# 6coils-1-discrete.net
KiCad netlist of a schematic drawn in EasyEDA
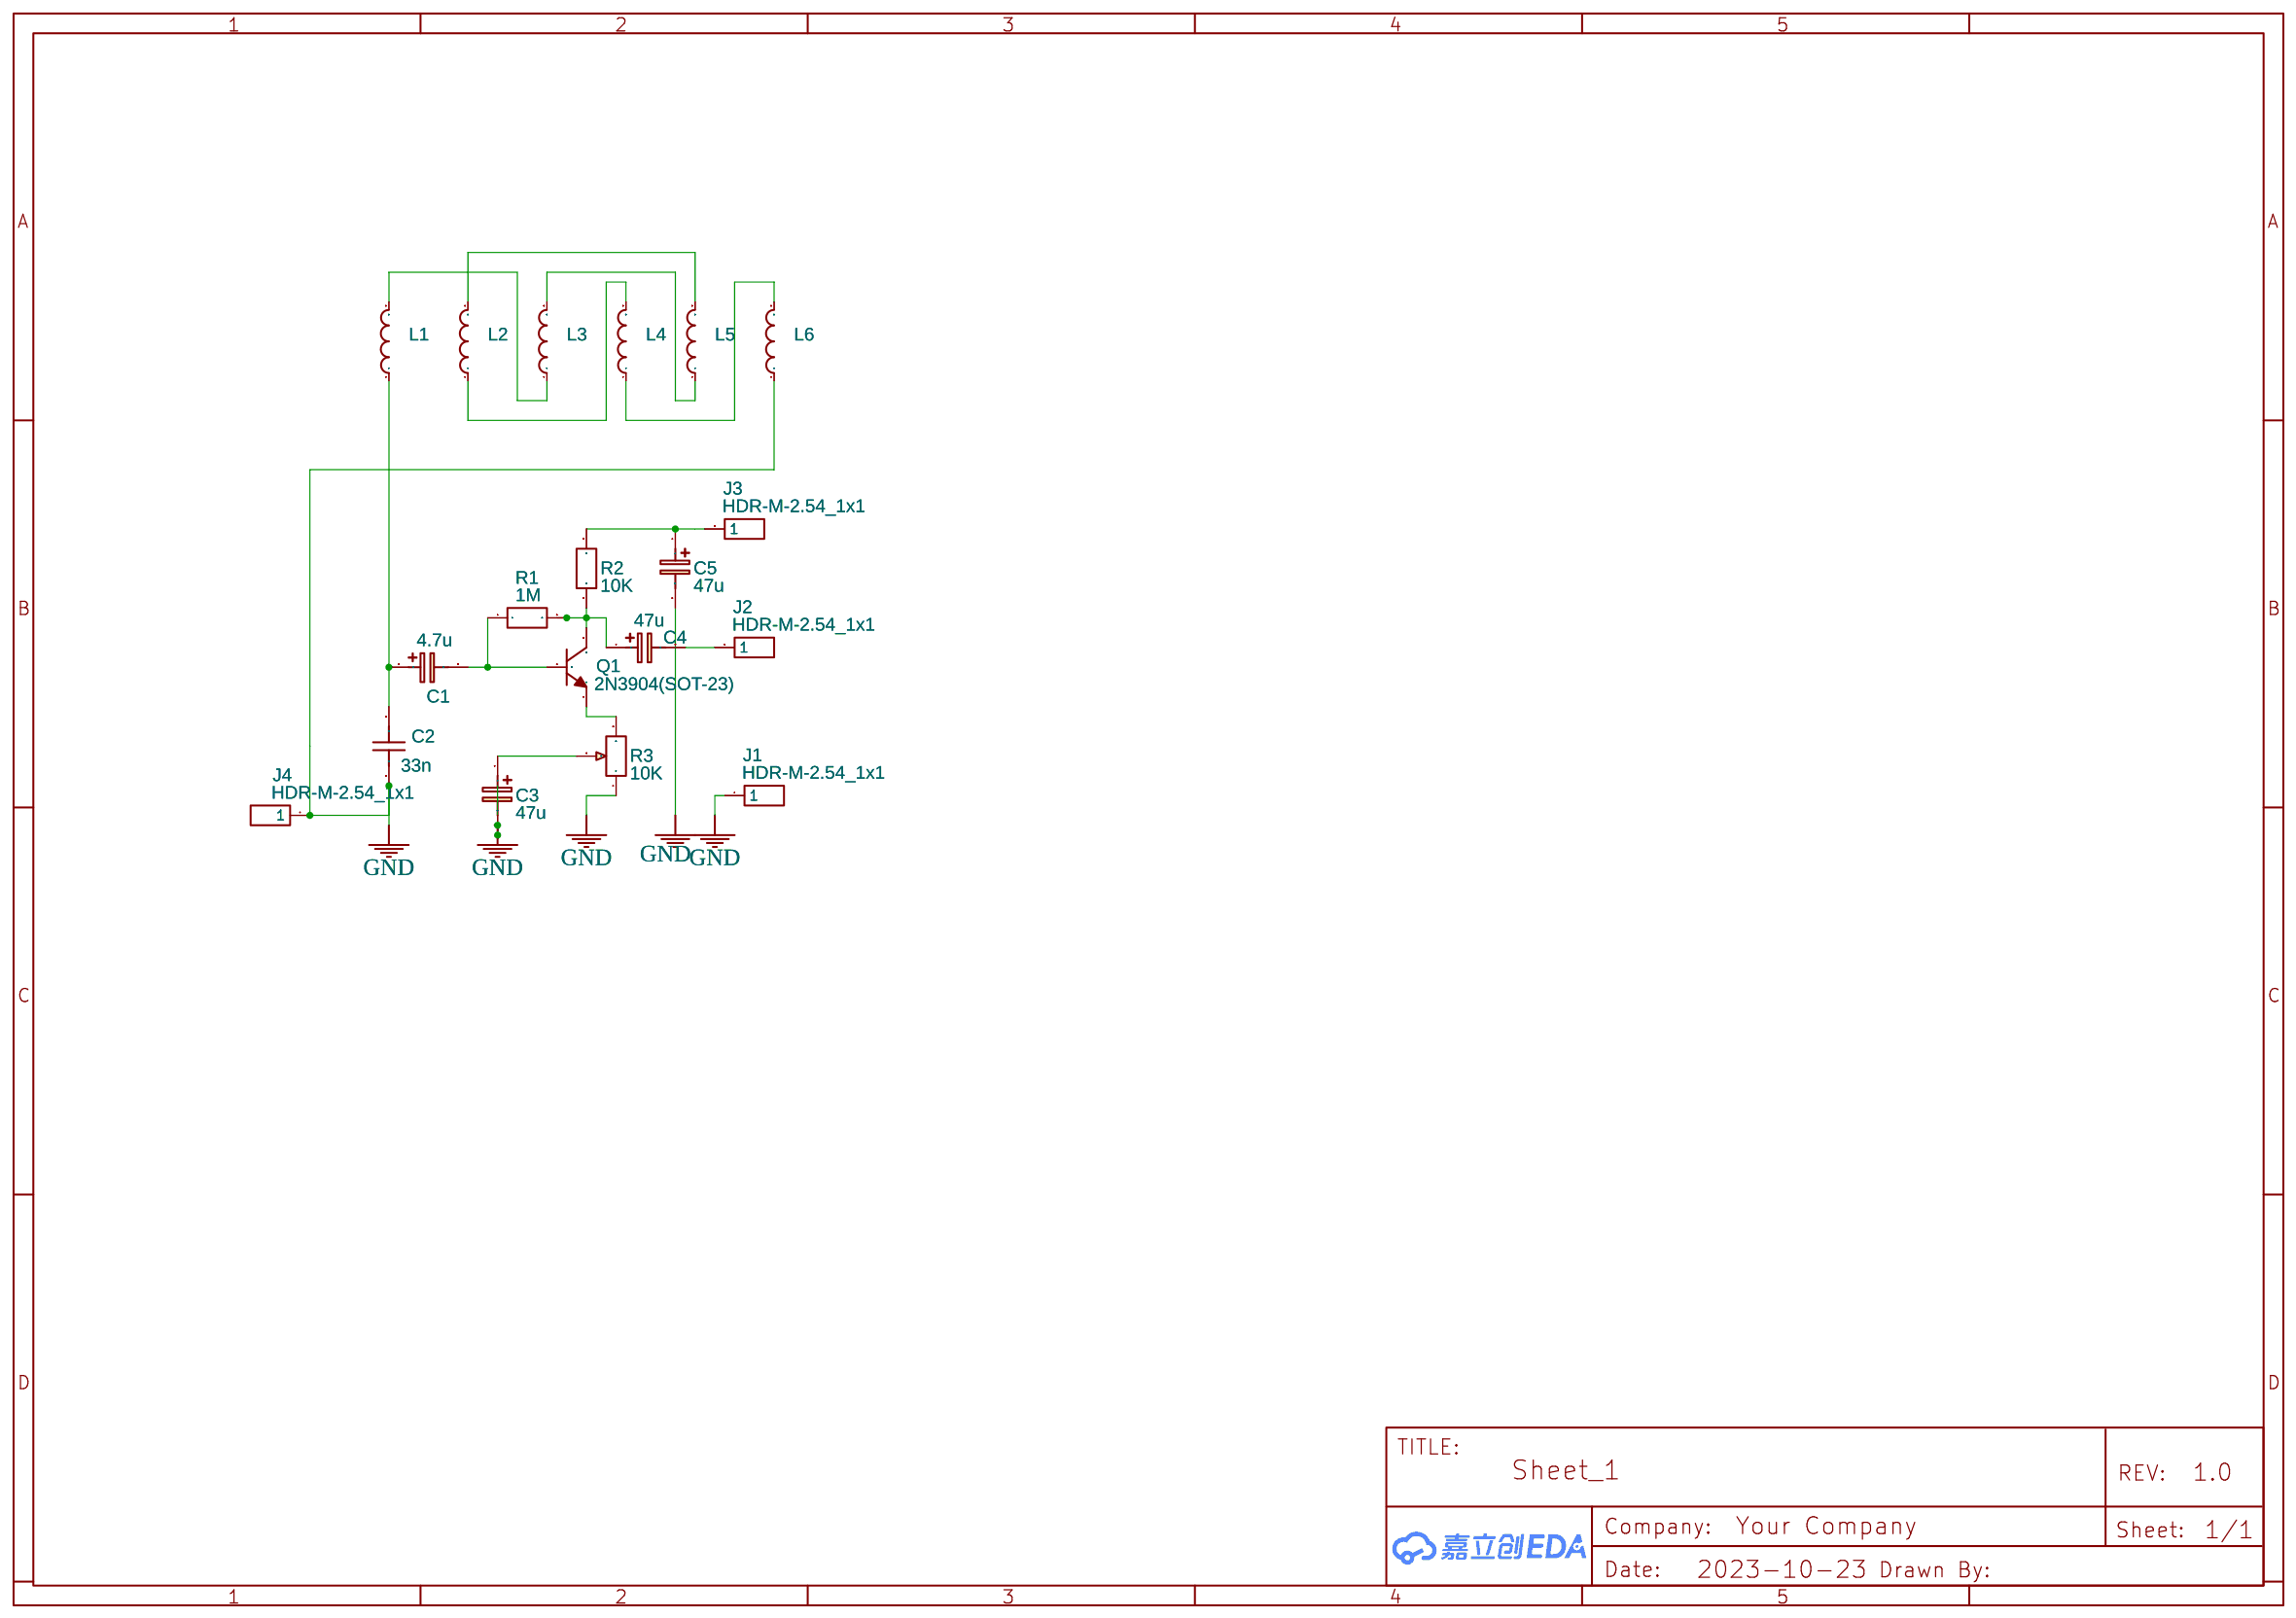
[diagram p0: schematic sheet]

(export (version "E")
  (design (tool "Eeschema 10.0.6"))
  (components
    (comp (ref "C1") (value "4.7u") (libsource (lib "") (part "C_Tan_SMD_A_EU_1")))
    (comp (ref "C2") (value "33n") (libsource (lib "") (part "C_0603_US")))
    (comp (ref "C3") (value "47u") (libsource (lib "") (part "C_Tan_SMD_A_EU")))
    (comp (ref "C4") (value "47u") (libsource (lib "") (part "C_Tan_SMD_A_EU_3")))
    (comp (ref "C5") (value "47u") (libsource (lib "") (part "C_Tan_SMD_A_EU_2")))
    (comp (ref "J1")
      (value "HDR-M-2.54_1x1")
      (fields (field (name "BOM_Supplier Part") "C81276"))
      (libsource (lib "") (part "HDR-M-2.54_1x1"))
    )
    (comp (ref "J2")
      (value "HDR-M-2.54_1x1")
      (fields (field (name "BOM_Supplier Part") "C81276"))
      (libsource (lib "") (part "HDR-M-2.54_1x1"))
    )
    (comp (ref "J3")
      (value "HDR-M-2.54_1x1")
      (fields (field (name "BOM_Supplier Part") "C81276"))
      (libsource (lib "") (part "HDR-M-2.54_1x1"))
    )
    (comp (ref "J4")
      (value "HDR-M-2.54_1x1")
      (fields (field (name "BOM_Supplier Part") "C81276"))
      (libsource (lib "") (part "HDR-M-2.54_1x1_1"))
    )
    (comp (ref "L1")
      (value "INDUCTOR_SMD:L_COILCRAFT_XXL4040")
      (fields (field (name "Manufacturer Part") "Inductor_SMD:L_Coilcraft_XxL4040"))
      (libsource (lib "") (part "INDUCTOR_SMD{colon}L_COILCRAFT_XXL4040_1"))
    )
    (comp (ref "L2")
      (value "INDUCTOR_SMD:L_COILCRAFT_XXL4040")
      (fields (field (name "Manufacturer Part") "Inductor_SMD:L_Coilcraft_XxL4040"))
      (libsource (lib "") (part "INDUCTOR_SMD{colon}L_COILCRAFT_XXL4040_1"))
    )
    (comp (ref "L3")
      (value "INDUCTOR_SMD:L_COILCRAFT_XXL4040")
      (fields (field (name "Manufacturer Part") "Inductor_SMD:L_Coilcraft_XxL4040"))
      (libsource (lib "") (part "INDUCTOR_SMD{colon}L_COILCRAFT_XXL4040"))
    )
    (comp (ref "L4")
      (value "INDUCTOR_SMD:L_COILCRAFT_XXL4040")
      (fields (field (name "Manufacturer Part") "Inductor_SMD:L_Coilcraft_XxL4040"))
      (libsource (lib "") (part "INDUCTOR_SMD{colon}L_COILCRAFT_XXL4040"))
    )
    (comp (ref "L5")
      (value "INDUCTOR_SMD:L_COILCRAFT_XXL4040")
      (fields (field (name "Manufacturer Part") "Inductor_SMD:L_Coilcraft_XxL4040"))
      (libsource (lib "") (part "INDUCTOR_SMD{colon}L_COILCRAFT_XXL4040"))
    )
    (comp (ref "L6")
      (value "INDUCTOR_SMD:L_COILCRAFT_XXL4040")
      (fields (field (name "Manufacturer Part") "Inductor_SMD:L_Coilcraft_XxL4040"))
      (libsource (lib "") (part "INDUCTOR_SMD{colon}L_COILCRAFT_XXL4040"))
    )
    (comp (ref "Q1")
      (value "2N3904(SOT-23)")
      (fields
        (field (name "BOM_Manufacturer Part") "2n3904S-RTK/PS")
        (field (name "BOM_Supplier Part") "C18536")
      )
      (libsource (lib "") (part "2N3904(SOT-23)"))
    )
    (comp (ref "R1") (value "1M") (libsource (lib "") (part "R_0603_EU_1")))
    (comp (ref "R2") (value "10K") (libsource (lib "") (part "R_0603_EU")))
    (comp (ref "R3")
      (value "10K")
      (fields (field (name "Manufacturer Part") "RM063-103 10K") (field (name "Manufacturer") "JML"))
      (libsource (lib "") (part "RM063-103 10K"))
    )
  )
  (nets
    (net (code "1") (name "GND") (class "Default")
      (node (ref "C2") (pin "1") (pinfunction "1_1") (pintype "unspecified"))
      (node (ref "C3") (pin "2") (pinfunction "2_2") (pintype "unspecified"))
      (node (ref "C5") (pin "2") (pinfunction "2_2") (pintype "unspecified"))
      (node (ref "J1") (pin "1") (pinfunction "1_1") (pintype "input"))
      (node (ref "J4") (pin "1") (pinfunction "1_1") (pintype "input"))
      (node (ref "L6") (pin "1") (pinfunction "1_1") (pintype "unspecified"))
      (node (ref "R3") (pin "1") (pinfunction "1_1") (pintype "input"))
    )
    (net (code "2") (name "Net-(C1-Pad1)") (class "Default")
      (node (ref "C1") (pin "1") (pinfunction "1_1") (pintype "unspecified"))
      (node (ref "C2") (pin "2") (pinfunction "2_2") (pintype "unspecified"))
      (node (ref "L1") (pin "1") (pinfunction "1_1") (pintype "unspecified"))
    )
    (net (code "3") (name "Net-(C3-Pad1)") (class "Default")
      (node (ref "C3") (pin "1") (pinfunction "1_1") (pintype "unspecified"))
      (node (ref "R3") (pin "2") (pinfunction "2_2") (pintype "input"))
    )
    (net (code "4") (name "Net-(C4-Pad2)") (class "Default")
      (node (ref "C4") (pin "2") (pinfunction "2_2") (pintype "unspecified"))
      (node (ref "J2") (pin "1") (pinfunction "1_1") (pintype "input"))
    )
    (net (code "5") (name "Net-(C5-Pad1)") (class "Default")
      (node (ref "C5") (pin "1") (pinfunction "1_1") (pintype "unspecified"))
      (node (ref "J3") (pin "1") (pinfunction "1_1") (pintype "input"))
      (node (ref "R2") (pin "2") (pinfunction "2_2") (pintype "unspecified"))
    )
    (net (code "6") (name "Net-(L1-Pad2)") (class "Default")
      (node (ref "L1") (pin "2") (pinfunction "2_2") (pintype "unspecified"))
      (node (ref "L3") (pin "1") (pinfunction "1_1") (pintype "unspecified"))
    )
    (net (code "7") (name "Net-(L2-Pad1)") (class "Default")
      (node (ref "L2") (pin "1") (pinfunction "1_1") (pintype "unspecified"))
      (node (ref "L4") (pin "2") (pinfunction "2_2") (pintype "unspecified"))
    )
    (net (code "8") (name "Net-(L2-Pad2)") (class "Default")
      (node (ref "L2") (pin "2") (pinfunction "2_2") (pintype "unspecified"))
      (node (ref "L5") (pin "2") (pinfunction "2_2") (pintype "unspecified"))
    )
    (net (code "9") (name "Net-(L3-Pad2)") (class "Default")
      (node (ref "L3") (pin "2") (pinfunction "2_2") (pintype "unspecified"))
      (node (ref "L5") (pin "1") (pinfunction "1_1") (pintype "unspecified"))
    )
    (net (code "10") (name "Net-(L4-Pad1)") (class "Default")
      (node (ref "L4") (pin "1") (pinfunction "1_1") (pintype "unspecified"))
      (node (ref "L6") (pin "2") (pinfunction "2_2") (pintype "unspecified"))
    )
    (net (code "11") (name "Net-(Q1-B)") (class "Default")
      (node (ref "C1") (pin "2") (pinfunction "2_2") (pintype "unspecified"))
      (node (ref "Q1") (pin "2") (pinfunction "B_2") (pintype "input"))
      (node (ref "R1") (pin "1") (pinfunction "1_1") (pintype "unspecified"))
    )
    (net (code "12") (name "Net-(Q1-C)") (class "Default")
      (node (ref "C4") (pin "1") (pinfunction "1_1") (pintype "unspecified"))
      (node (ref "Q1") (pin "3") (pinfunction "C_3") (pintype "input"))
      (node (ref "R1") (pin "2") (pinfunction "2_2") (pintype "unspecified"))
      (node (ref "R2") (pin "1") (pinfunction "1_1") (pintype "unspecified"))
    )
    (net (code "13") (name "Net-(Q1-E)") (class "Default")
      (node (ref "Q1") (pin "1") (pinfunction "E_1") (pintype "input"))
      (node (ref "R3") (pin "3") (pinfunction "3_3") (pintype "input"))
    )
  )
)
